# H204_R_Sensors.net
KiCad netlist of a schematic drawn in Altium Designer
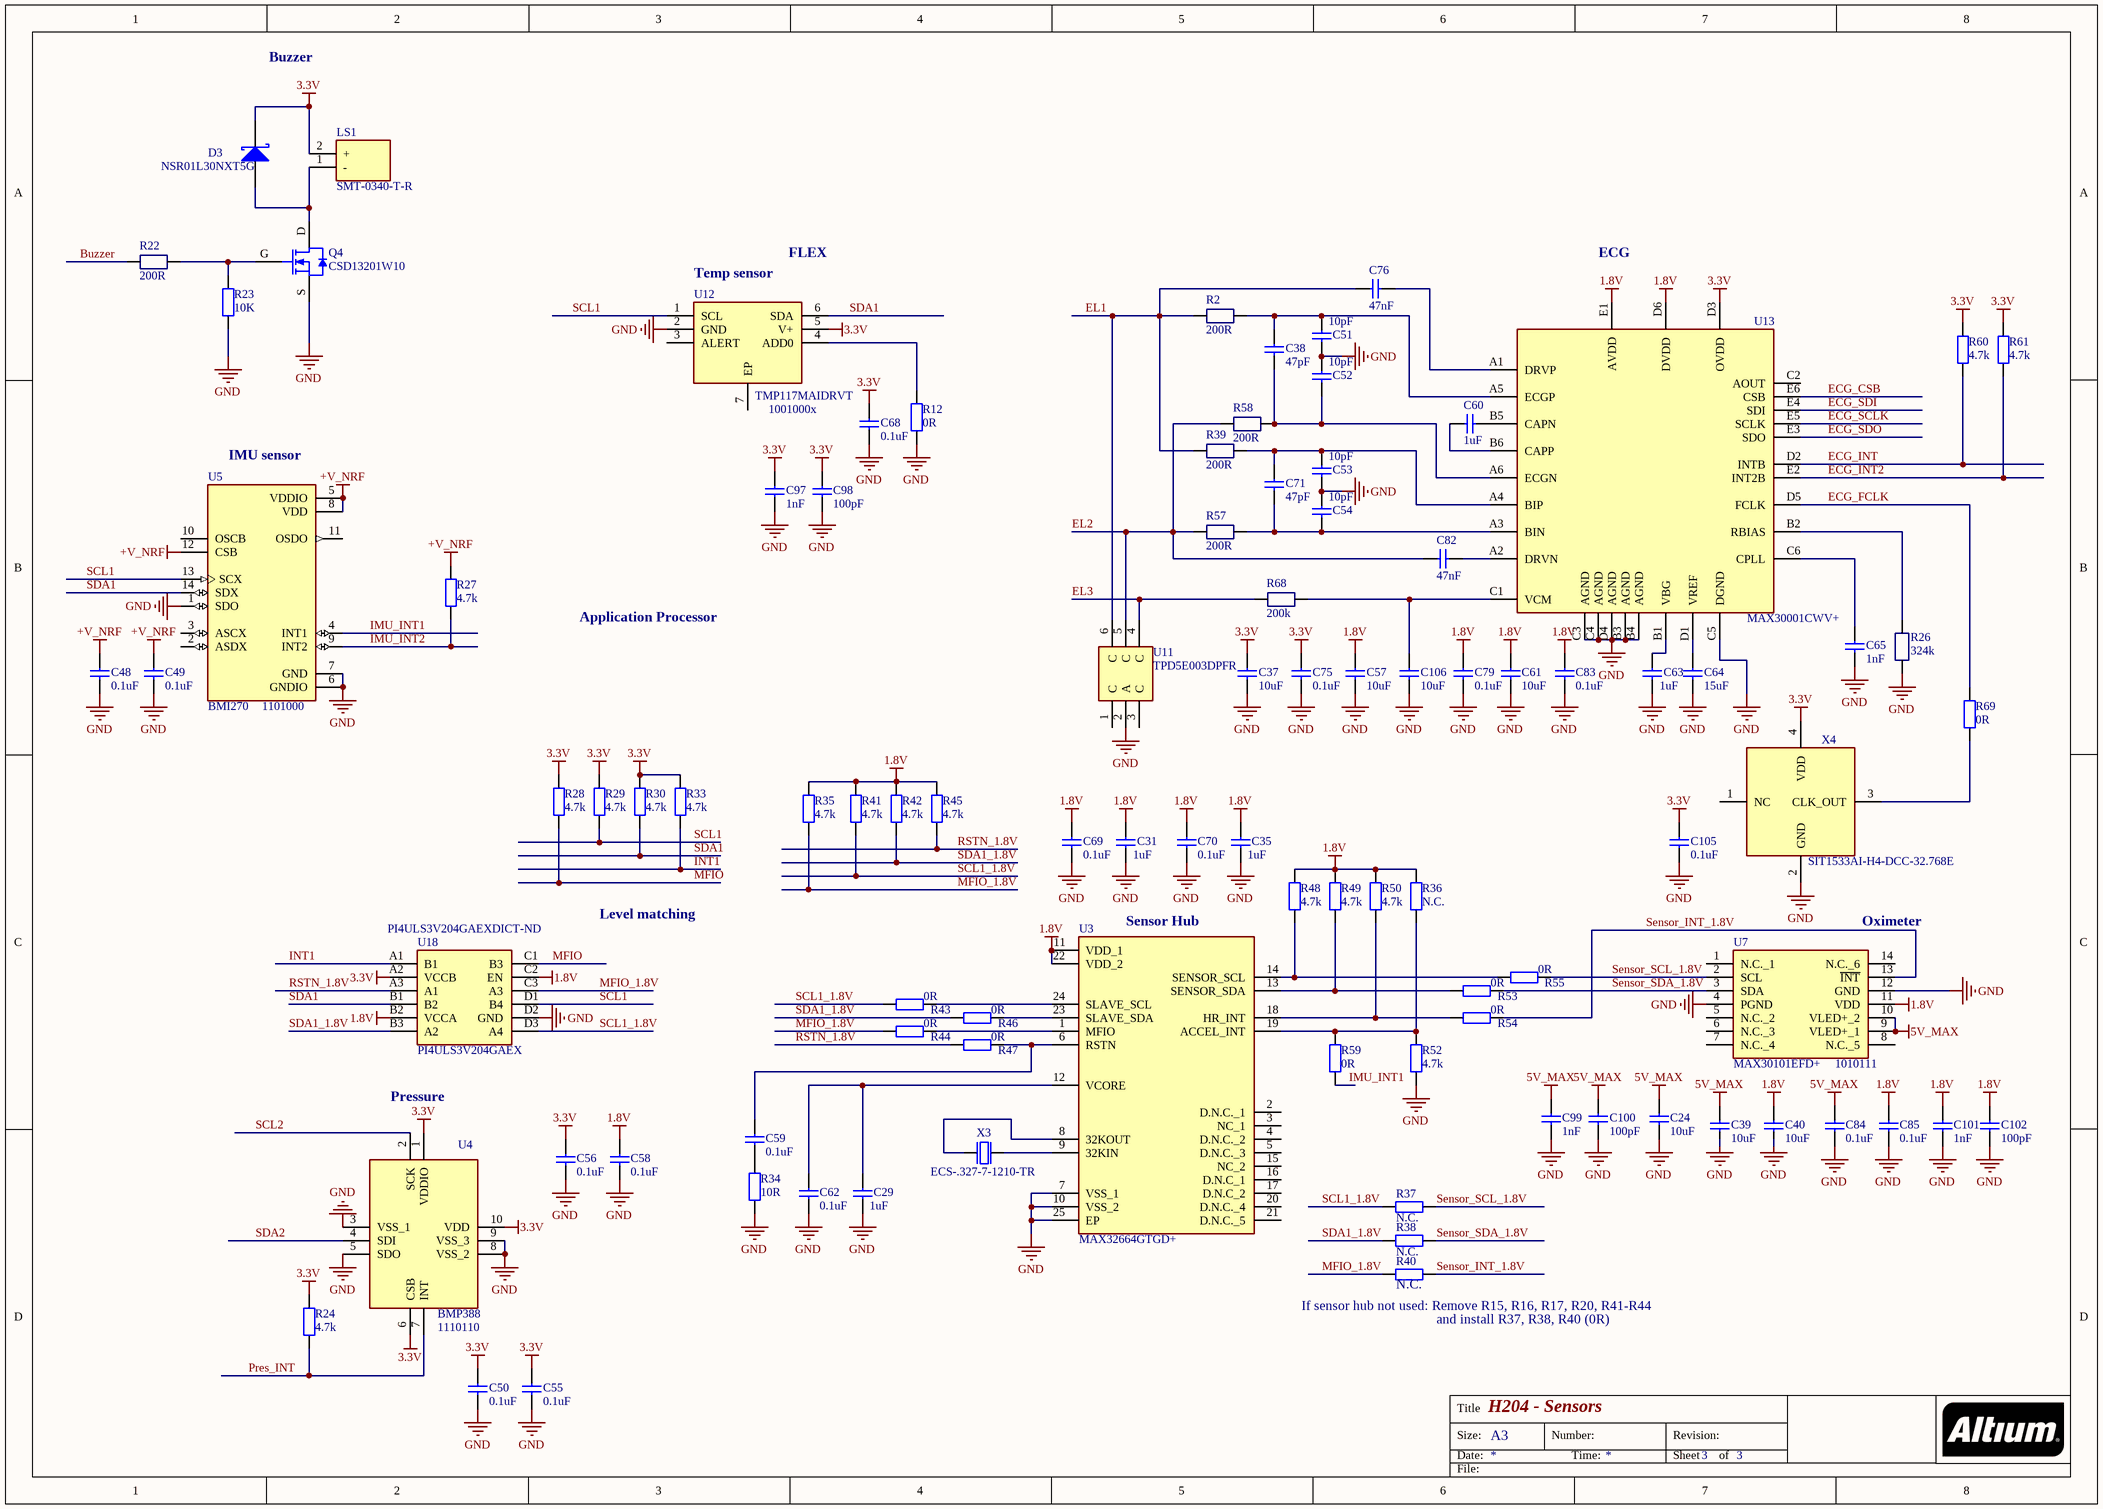
[diagram p0: H204_R_Sensors.SchDoc]

(export (version "E")
  (design (tool "Eeschema 10.0.6"))
  (components
    (comp (ref "C24")
      (value "10uF")
      (footprint "CAPC1005X55N")
      (description "CAP CER 10UF 10V X5R 0402")
      (fields
        (field (name "MANUFACTURER") "Samsung")
        (field (name "MANUFACTURER PART NUMBER") "CL05A106MP8NUB8")
      )
      (libsource (lib "Nordic Passive DB") (part "CAP"))
    )
    (comp (ref "C29")
      (value "1uF")
      (footprint "CAPC0603X33N")
      (description "CAP CER 1UF 6.3V X5R 0201")
      (fields
        (field (name "MANUFACTURER") "Samsung")
        (field (name "MANUFACTURER PART NUMBER") "CL03A105MQ3CSNC")
      )
      (libsource (lib "AltiumLib") (part "CAP"))
    )
    (comp (ref "C31")
      (value "1uF")
      (footprint "CAPC0603X33N")
      (description "CAP CER 1UF 6.3V X5R 0201")
      (fields
        (field (name "MANUFACTURER") "Samsung")
        (field (name "MANUFACTURER PART NUMBER") "CL03A105MQ3CSNC")
      )
      (libsource (lib "AltiumLib") (part "CAP"))
    )
    (comp (ref "C35")
      (value "1uF")
      (footprint "CAPC0603X33N")
      (description "CAP CER 1UF 6.3V X5R 0201")
      (fields
        (field (name "MANUFACTURER") "Samsung")
        (field (name "MANUFACTURER PART NUMBER") "CL03A105MQ3CSNC")
      )
      (libsource (lib "AltiumLib") (part "CAP"))
    )
    (comp (ref "C37")
      (value "10uF")
      (footprint "CAPC1005X55N")
      (description "CAP CER 10UF 10V X5R 0402")
      (fields
        (field (name "MANUFACTURER") "Samsung")
        (field (name "MANUFACTURER PART NUMBER") "CL05A106MP8NUB8")
      )
      (libsource (lib "Nordic Passive DB") (part "CAP"))
    )
    (comp (ref "C38")
      (value "47pF")
      (footprint "CAPC0603X33N")
      (description "Cap Ceramic Monolithic 47pF 50VDC 1% SMD Paper T/R")
      (fields
        (field (name "MANUFACTURER") "Murata")
        (field (name "MANUFACTURER PART NUMBER") "GRM0335C1H470FA01D")
      )
      (libsource (lib "Nordic Passive DB") (part "CAP"))
    )
    (comp (ref "C39")
      (value "10uF")
      (footprint "CAPC1005X55N")
      (description "CAP CER 10UF 10V X5R 0402")
      (fields
        (field (name "MANUFACTURER") "Samsung")
        (field (name "MANUFACTURER PART NUMBER") "CL05A106MP8NUB8")
      )
      (libsource (lib "Nordic Passive DB") (part "CAP"))
    )
    (comp (ref "C40")
      (value "10uF")
      (footprint "CAPC1005X55N")
      (description "CAP CER 10UF 10V X5R 0402")
      (fields
        (field (name "MANUFACTURER") "Samsung")
        (field (name "MANUFACTURER PART NUMBER") "CL05A106MP8NUB8")
      )
      (libsource (lib "Nordic Passive DB") (part "CAP"))
    )
    (comp (ref "C48")
      (value "0.1uF")
      (footprint "CAPC0603X33N")
      (description "CAP CER 0.1UF 16V X5R 0201")
      (fields
        (field (name "MANUFACTURER") "Samsung")
        (field (name "MANUFACTURER PART NUMBER") "CL03A104KO3NNNC")
      )
      (libsource (lib "AltiumLib") (part "CAP"))
    )
    (comp (ref "C49")
      (value "0.1uF")
      (footprint "CAPC0603X33N")
      (description "CAP CER 0.1UF 16V X5R 0201")
      (fields
        (field (name "MANUFACTURER") "Samsung")
        (field (name "MANUFACTURER PART NUMBER") "CL03A104KO3NNNC")
      )
      (libsource (lib "AltiumLib") (part "CAP"))
    )
    (comp (ref "C50")
      (value "0.1uF")
      (footprint "CAPC0603X33N")
      (description "CAP CER 0.1UF 16V X5R 0201")
      (fields
        (field (name "MANUFACTURER") "Samsung")
        (field (name "MANUFACTURER PART NUMBER") "CL03A104KO3NNNC")
      )
      (libsource (lib "AltiumLib") (part "CAP"))
    )
    (comp (ref "C51")
      (value "10pF")
      (footprint "CAPC0603X33N")
      (fields
        (field (name "MANUFACTURER") "Murata")
        (field (name "MANUFACTURER PART NUMBER") "GRM0335C1H100JA01D")
        (field (name "TOLERANCE") "5%")
      )
      (libsource (lib "Nordic Passive DB") (part "CAP"))
    )
    (comp (ref "C52")
      (value "10pF")
      (footprint "CAPC0603X33N")
      (fields
        (field (name "MANUFACTURER") "Murata")
        (field (name "MANUFACTURER PART NUMBER") "GRM0335C1H100JA01D")
        (field (name "TOLERANCE") "5%")
      )
      (libsource (lib "Nordic Passive DB") (part "CAP"))
    )
    (comp (ref "C53")
      (value "10pF")
      (footprint "CAPC0603X33N")
      (fields
        (field (name "MANUFACTURER") "Murata")
        (field (name "MANUFACTURER PART NUMBER") "GRM0335C1H100JA01D")
        (field (name "TOLERANCE") "5%")
      )
      (libsource (lib "Nordic Passive DB") (part "CAP"))
    )
    (comp (ref "C54")
      (value "10pF")
      (footprint "CAPC0603X33N")
      (fields
        (field (name "MANUFACTURER") "Murata")
        (field (name "MANUFACTURER PART NUMBER") "GRM0335C1H100JA01D")
        (field (name "TOLERANCE") "5%")
      )
      (libsource (lib "Nordic Passive DB") (part "CAP"))
    )
    (comp (ref "C55")
      (value "0.1uF")
      (footprint "CAPC0603X33N")
      (description "CAP CER 0.1UF 16V X5R 0201")
      (fields
        (field (name "MANUFACTURER") "Samsung")
        (field (name "MANUFACTURER PART NUMBER") "CL03A104KO3NNNC")
      )
      (libsource (lib "AltiumLib") (part "CAP"))
    )
    (comp (ref "C56")
      (value "0.1uF")
      (footprint "CAPC0603X33N")
      (description "CAP CER 0.1UF 16V X5R 0201")
      (fields
        (field (name "MANUFACTURER") "Samsung")
        (field (name "MANUFACTURER PART NUMBER") "CL03A104KO3NNNC")
      )
      (libsource (lib "AltiumLib") (part "CAP"))
    )
    (comp (ref "C57")
      (value "10uF")
      (footprint "CAPC1005X55N")
      (description "CAP CER 10UF 10V X5R 0402")
      (fields
        (field (name "MANUFACTURER") "Samsung")
        (field (name "MANUFACTURER PART NUMBER") "CL05A106MP8NUB8")
      )
      (libsource (lib "Nordic Passive DB") (part "CAP"))
    )
    (comp (ref "C58")
      (value "0.1uF")
      (footprint "CAPC0603X33N")
      (description "CAP CER 0.1UF 16V X5R 0201")
      (fields
        (field (name "MANUFACTURER") "Samsung")
        (field (name "MANUFACTURER PART NUMBER") "CL03A104KO3NNNC")
      )
      (libsource (lib "AltiumLib") (part "CAP"))
    )
    (comp (ref "C59")
      (value "0.1uF")
      (footprint "CAPC0603X33N")
      (description "CAP CER 0.1UF 16V X5R 0201")
      (fields
        (field (name "MANUFACTURER") "Samsung")
        (field (name "MANUFACTURER PART NUMBER") "CL03A104KO3NNNC")
      )
      (libsource (lib "AltiumLib") (part "CAP"))
    )
    (comp (ref "C60")
      (value "1uF")
      (footprint "CAPC0603X33N")
      (description "CAP CER 1UF 6.3V X5R 0201")
      (fields
        (field (name "MANUFACTURER") "Samsung")
        (field (name "MANUFACTURER PART NUMBER") "CL03A105MQ3CSNC")
      )
      (libsource (lib "AltiumLib") (part "CAP"))
    )
    (comp (ref "C61")
      (value "10uF")
      (footprint "CAPC1005X55N")
      (description "CAP CER 10UF 10V X5R 0402")
      (fields
        (field (name "MANUFACTURER") "Samsung")
        (field (name "MANUFACTURER PART NUMBER") "CL05A106MP8NUB8")
      )
      (libsource (lib "Nordic Passive DB") (part "CAP"))
    )
    (comp (ref "C62")
      (value "0.1uF")
      (footprint "CAPC0603X33N")
      (description "CAP CER 0.1UF 16V X5R 0201")
      (fields
        (field (name "MANUFACTURER") "Samsung")
        (field (name "MANUFACTURER PART NUMBER") "CL03A104KO3NNNC")
      )
      (libsource (lib "AltiumLib") (part "CAP"))
    )
    (comp (ref "C63")
      (value "1uF")
      (footprint "CAPC0603X33N")
      (description "CAP CER 1UF 6.3V X5R 0201")
      (fields
        (field (name "MANUFACTURER") "Samsung")
        (field (name "MANUFACTURER PART NUMBER") "CL03A105MQ3CSNC")
      )
      (libsource (lib "AltiumLib") (part "CAP"))
    )
    (comp (ref "C64")
      (value "15uF")
      (footprint "CAPC1005X55N")
      (description "Cap Ceramic Monolithic 15uF 6.3VDC 20% SMD Paper T/R")
      (fields
        (field (name "MANUFACTURER") "Murata")
        (field (name "MANUFACTURER PART NUMBER") "GRM155R60J156ME05D")
      )
      (libsource (lib "Nordic Passive DB") (part "CAP"))
    )
    (comp (ref "C65")
      (value "1nF")
      (footprint "CAPC0603X33N")
      (description "Cap Ceramic 0.001uF 25V X7R 10% SMD 0201 125C Paper T/R")
      (fields
        (field (name "MANUFACTURER") "Samsung")
        (field (name "MANUFACTURER PART NUMBER") "CL03B102KA3NNNC")
      )
      (libsource (lib "Nordic Passive DB") (part "CAP"))
    )
    (comp (ref "C68")
      (value "0.1uF")
      (footprint "CAPC0603X33N")
      (description "CAP CER 0.1UF 16V X5R 0201")
      (fields
        (field (name "MANUFACTURER") "Samsung")
        (field (name "MANUFACTURER PART NUMBER") "CL03A104KO3NNNC")
      )
      (libsource (lib "AltiumLib") (part "CAP"))
    )
    (comp (ref "C69")
      (value "0.1uF")
      (footprint "CAPC0603X33N")
      (description "CAP CER 0.1UF 16V X5R 0201")
      (fields
        (field (name "MANUFACTURER") "Samsung")
        (field (name "MANUFACTURER PART NUMBER") "CL03A104KO3NNNC")
      )
      (libsource (lib "AltiumLib") (part "CAP"))
    )
    (comp (ref "C70")
      (value "0.1uF")
      (footprint "CAPC0603X33N")
      (description "CAP CER 0.1UF 16V X5R 0201")
      (fields
        (field (name "MANUFACTURER") "Samsung")
        (field (name "MANUFACTURER PART NUMBER") "CL03A104KO3NNNC")
      )
      (libsource (lib "AltiumLib") (part "CAP"))
    )
    (comp (ref "C71")
      (value "47pF")
      (footprint "CAPC0603X33N")
      (description "Cap Ceramic Monolithic 47pF 50VDC 1% SMD Paper T/R")
      (fields
        (field (name "MANUFACTURER") "Murata")
        (field (name "MANUFACTURER PART NUMBER") "GRM0335C1H470FA01D")
      )
      (libsource (lib "Nordic Passive DB") (part "CAP"))
    )
    (comp (ref "C75")
      (value "0.1uF")
      (footprint "CAPC0603X33N")
      (description "CAP CER 0.1UF 16V X5R 0201")
      (fields
        (field (name "MANUFACTURER") "Samsung")
        (field (name "MANUFACTURER PART NUMBER") "CL03A104KO3NNNC")
      )
      (libsource (lib "AltiumLib") (part "CAP"))
    )
    (comp (ref "C76")
      (value "47nF")
      (footprint "CAPC0603X33N")
      (description "CAP CER 0.047UF 25V X5R 0201")
      (fields
        (field (name "MANUFACTURER") "TDK")
        (field (name "MANUFACTURER PART NUMBER") "C0603X5R1E473K030BB")
      )
      (libsource (lib "Nordic Passive DB") (part "CAP"))
    )
    (comp (ref "C79")
      (value "0.1uF")
      (footprint "CAPC0603X33N")
      (description "CAP CER 0.1UF 16V X5R 0201")
      (fields
        (field (name "MANUFACTURER") "Samsung")
        (field (name "MANUFACTURER PART NUMBER") "CL03A104KO3NNNC")
      )
      (libsource (lib "AltiumLib") (part "CAP"))
    )
    (comp (ref "C82")
      (value "47nF")
      (footprint "CAPC0603X33N")
      (description "CAP CER 0.047UF 25V X5R 0201")
      (fields
        (field (name "MANUFACTURER") "TDK")
        (field (name "MANUFACTURER PART NUMBER") "C0603X5R1E473K030BB")
      )
      (libsource (lib "Nordic Passive DB") (part "CAP"))
    )
    (comp (ref "C83")
      (value "0.1uF")
      (footprint "CAPC0603X33N")
      (description "CAP CER 0.1UF 16V X5R 0201")
      (fields
        (field (name "MANUFACTURER") "Samsung")
        (field (name "MANUFACTURER PART NUMBER") "CL03A104KO3NNNC")
      )
      (libsource (lib "AltiumLib") (part "CAP"))
    )
    (comp (ref "C84")
      (value "0.1uF")
      (footprint "CAPC0603X33N")
      (description "CAP CER 0.1UF 16V X5R 0201")
      (fields
        (field (name "MANUFACTURER") "Samsung")
        (field (name "MANUFACTURER PART NUMBER") "CL03A104KO3NNNC")
      )
      (libsource (lib "AltiumLib") (part "CAP"))
    )
    (comp (ref "C85")
      (value "0.1uF")
      (footprint "CAPC0603X33N")
      (description "CAP CER 0.1UF 16V X5R 0201")
      (fields
        (field (name "MANUFACTURER") "Samsung")
        (field (name "MANUFACTURER PART NUMBER") "CL03A104KO3NNNC")
      )
      (libsource (lib "AltiumLib") (part "CAP"))
    )
    (comp (ref "C97")
      (value "1nF")
      (footprint "CAPC0603X33N")
      (description "Cap Ceramic 0.001uF 25V X7R 10% SMD 0201 125C Paper T/R")
      (fields
        (field (name "MANUFACTURER") "Samsung")
        (field (name "MANUFACTURER PART NUMBER") "CL03B102KA3NNNC")
      )
      (libsource (lib "Nordic Passive DB") (part "CAP"))
    )
    (comp (ref "C98")
      (value "100pF")
      (footprint "CAPC0603X33N")
      (description "CAP CER 100PF 50V C0G 0201")
      (fields
        (field (name "MANUFACTURER") "TDK")
        (field (name "MANUFACTURER PART NUMBER") "C0603C0G1H101J030BA")
      )
      (libsource (lib "Nordic Passive DB") (part "CAP"))
    )
    (comp (ref "C99")
      (value "1nF")
      (footprint "CAPC0603X33N")
      (description "Cap Ceramic 0.001uF 25V X7R 10% SMD 0201 125C Paper T/R")
      (fields
        (field (name "MANUFACTURER") "Samsung")
        (field (name "MANUFACTURER PART NUMBER") "CL03B102KA3NNNC")
      )
      (libsource (lib "Nordic Passive DB") (part "CAP"))
    )
    (comp (ref "C100")
      (value "100pF")
      (footprint "CAPC0603X33N")
      (description "CAP CER 100PF 50V C0G 0201")
      (fields
        (field (name "MANUFACTURER") "TDK")
        (field (name "MANUFACTURER PART NUMBER") "C0603C0G1H101J030BA")
      )
      (libsource (lib "Nordic Passive DB") (part "CAP"))
    )
    (comp (ref "C101")
      (value "1nF")
      (footprint "CAPC0603X33N")
      (description "Cap Ceramic 0.001uF 25V X7R 10% SMD 0201 125C Paper T/R")
      (fields
        (field (name "MANUFACTURER") "Samsung")
        (field (name "MANUFACTURER PART NUMBER") "CL03B102KA3NNNC")
      )
      (libsource (lib "Nordic Passive DB") (part "CAP"))
    )
    (comp (ref "C102")
      (value "100pF")
      (footprint "CAPC0603X33N")
      (description "CAP CER 100PF 50V C0G 0201")
      (fields
        (field (name "MANUFACTURER") "TDK")
        (field (name "MANUFACTURER PART NUMBER") "C0603C0G1H101J030BA")
      )
      (libsource (lib "Nordic Passive DB") (part "CAP"))
    )
    (comp (ref "C105")
      (value "0.1uF")
      (footprint "CAPC0603X33N")
      (description "CAP CER 0.1UF 16V X5R 0201")
      (fields
        (field (name "MANUFACTURER") "Samsung")
        (field (name "MANUFACTURER PART NUMBER") "CL03A104KO3NNNC")
      )
      (libsource (lib "AltiumLib") (part "CAP"))
    )
    (comp (ref "C106")
      (value "10uF")
      (footprint "CAPC1005X55N")
      (description "CAP CER 10UF 10V X5R 0402")
      (fields
        (field (name "MANUFACTURER") "Samsung")
        (field (name "MANUFACTURER PART NUMBER") "CL05A106MP8NUB8")
      )
      (libsource (lib "Nordic Passive DB") (part "CAP"))
    )
    (comp (ref "D3")
      (value "NSR01L30NXT5G")
      (footprint "NSR01L30NXT5G")
      (fields (field (name "MANUFACTURER") "ON Semiconductor"))
      (libsource (lib "Diodes - Bridge Rectifiers") (part "Schottky"))
    )
    (comp (ref "LS1")
      (value "SMT-0340-T-R")
      (footprint "SMT0340TR")
      (description "Loudspeaker or Buzzer")
      (fields
        (field (name "MANUFACTURER") "PUI Audio")
        (field (name "MOUSER PART NUMBER") "665-SMT-0340-T-R")
      )
      (libsource (lib "*") (part "SMT-0340-T-R"))
    )
    (comp (ref "Q4")
      (value "CSD13201W10")
      (footprint "CSD13201W10")
      (description "12V, N ch NexFET MOSFET™, single WLP 1.0x1.0, 34mOhm 4-DSBGA -55 to 150")
      (fields (field (name "MANUFACTURER") "Texas Instruments"))
      (libsource (lib "Transistors") (part "Transistor N-channel"))
    )
    (comp (ref "R2")
      (value "200R")
      (footprint "RESC0603X26N")
      (description "RES SMD 200 OHM 1% 1/20W 0201")
      (fields
        (field (name "MANUFACTURER") "Yageo")
        (field (name "MANUFACTURER PART NUMBER") "RC0201FR-07200RL")
      )
      (libsource (lib "Passive components") (part "Resistor"))
    )
    (comp (ref "R12")
      (value "0R")
      (footprint "RESC0603X26N")
      (description "Fixed Resistor, Metal Glaze/thick Film, 0.05W, 0ohm, Surface Mount, 0201")
      (fields
        (field (name "MANUFACTURER") "Yageo")
        (field (name "MANUFACTURER PART NUMBER") "AF0201JR-070RL")
      )
      (libsource (lib "") (part "Res2_2"))
    )
    (comp (ref "R22")
      (value "200R")
      (footprint "RESC0603X26N")
      (description "RES SMD 200 OHM 1% 1/20W 0201")
      (fields
        (field (name "MANUFACTURER") "Yageo")
        (field (name "MANUFACTURER PART NUMBER") "RC0201FR-07200RL")
      )
      (libsource (lib "Passive components") (part "Resistor"))
    )
    (comp (ref "R23")
      (value "10K")
      (footprint "RESC0603X26N")
      (description "GENERAL 0201 11% REEL (7INCH)")
      (fields
        (field (name "MANUFACTURER") "Yageo")
        (field (name "MANUFACTURER PART NUMBER") "RC0201FR-0710KL")
      )
      (libsource (lib "") (part "Res2_3"))
    )
    (comp (ref "R24")
      (value "4.7k")
      (footprint "RESC0603X26N")
      (description "GENERAL 0201 11% REEL (7INCH)")
      (fields
        (field (name "MANUFACTURER") "Yageo")
        (field (name "MANUFACTURER PART NUMBER") "RC0201FR-074K7L")
      )
      (libsource (lib "Miscellaneous Devices") (part "Res2"))
    )
    (comp (ref "R26")
      (value "324k")
      (footprint "RESC0603X26N")
      (description "Res Thick Film 0201 324K Ohm 1% 1/20W ±200ppm/°C Molded SMD Paper T/R")
      (fields
        (field (name "MANUFACTURER") "Yageo")
        (field (name "MANUFACTURER PART NUMBER") "RC0201FR-07324KL")
      )
      (libsource (lib "Passive components") (part "Resistor"))
    )
    (comp (ref "R27")
      (value "4.7k")
      (footprint "RESC0603X26N")
      (description "GENERAL 0201 11% REEL (7INCH)")
      (fields
        (field (name "MANUFACTURER") "Yageo")
        (field (name "MANUFACTURER PART NUMBER") "RC0201FR-074K7L")
      )
      (libsource (lib "Miscellaneous Devices") (part "Res2"))
    )
    (comp (ref "R28")
      (value "4.7k")
      (footprint "RESC0603X26N")
      (description "GENERAL 0201 11% REEL (7INCH)")
      (fields
        (field (name "MANUFACTURER") "Yageo")
        (field (name "MANUFACTURER PART NUMBER") "RC0201FR-074K7L")
      )
      (libsource (lib "Miscellaneous Devices") (part "Res2"))
    )
    (comp (ref "R29")
      (value "4.7k")
      (footprint "RESC0603X26N")
      (description "GENERAL 0201 11% REEL (7INCH)")
      (fields
        (field (name "MANUFACTURER") "Yageo")
        (field (name "MANUFACTURER PART NUMBER") "RC0201FR-074K7L")
      )
      (libsource (lib "Miscellaneous Devices") (part "Res2"))
    )
    (comp (ref "R30")
      (value "4.7k")
      (footprint "RESC0603X26N")
      (description "GENERAL 0201 11% REEL (7INCH)")
      (fields
        (field (name "MANUFACTURER") "Yageo")
        (field (name "MANUFACTURER PART NUMBER") "RC0201FR-074K7L")
      )
      (libsource (lib "Miscellaneous Devices") (part "Res2"))
    )
    (comp (ref "R33")
      (value "4.7k")
      (footprint "RESC0603X26N")
      (description "GENERAL 0201 11% REEL (7INCH)")
      (fields
        (field (name "MANUFACTURER") "Yageo")
        (field (name "MANUFACTURER PART NUMBER") "RC0201FR-074K7L")
      )
      (libsource (lib "Miscellaneous Devices") (part "Res2"))
    )
    (comp (ref "R34")
      (value "10R")
      (footprint "RESC0603X26N")
      (description "RES SMD 10 OHM 1% 1/20W 0201")
      (fields
        (field (name "MANUFACTURER") "Yageo")
        (field (name "MANUFACTURER PART NUMBER") "RC0201FR-0710RL")
      )
      (libsource (lib "") (part "Res2_3"))
    )
    (comp (ref "R35")
      (value "4.7k")
      (footprint "RESC0603X26N")
      (description "GENERAL 0201 11% REEL (7INCH)")
      (fields
        (field (name "MANUFACTURER") "Yageo")
        (field (name "MANUFACTURER PART NUMBER") "RC0201FR-074K7L")
      )
      (libsource (lib "Miscellaneous Devices") (part "Res2"))
    )
    (comp (ref "R36")
      (value "N.C.")
      (footprint "RESC0603X26N")
      (description "Resistor")
      (libsource (lib "") (part "Res2_3"))
    )
    (comp (ref "R37")
      (value "N.C.")
      (footprint "RESC0603X26N")
      (description "Resistor")
      (libsource (lib "Miscellaneous Devices") (part "Res2"))
    )
    (comp (ref "R38")
      (value "N.C.")
      (footprint "RESC0603X26N")
      (description "Resistor")
      (libsource (lib "Miscellaneous Devices") (part "Res2"))
    )
    (comp (ref "R39")
      (value "200R")
      (footprint "RESC0603X26N")
      (description "RES SMD 200 OHM 1% 1/20W 0201")
      (fields
        (field (name "MANUFACTURER") "Yageo")
        (field (name "MANUFACTURER PART NUMBER") "RC0201FR-07200RL")
      )
      (libsource (lib "Passive components") (part "Resistor"))
    )
    (comp (ref "R40")
      (value "N.C.")
      (footprint "RESC0603X26N")
      (description "Resistor")
      (libsource (lib "Miscellaneous Devices") (part "Res2"))
    )
    (comp (ref "R41")
      (value "4.7k")
      (footprint "RESC0603X26N")
      (description "GENERAL 0201 11% REEL (7INCH)")
      (fields
        (field (name "MANUFACTURER") "Yageo")
        (field (name "MANUFACTURER PART NUMBER") "RC0201FR-074K7L")
      )
      (libsource (lib "Miscellaneous Devices") (part "Res2"))
    )
    (comp (ref "R42")
      (value "4.7k")
      (footprint "RESC0603X26N")
      (description "GENERAL 0201 11% REEL (7INCH)")
      (fields
        (field (name "MANUFACTURER") "Yageo")
        (field (name "MANUFACTURER PART NUMBER") "RC0201FR-074K7L")
      )
      (libsource (lib "Miscellaneous Devices") (part "Res2"))
    )
    (comp (ref "R43")
      (value "0R")
      (footprint "RESC0603X26N")
      (description "Fixed Resistor, Metal Glaze/thick Film, 0.05W, 0ohm, Surface Mount, 0201")
      (fields
        (field (name "MANUFACTURER") "Yageo")
        (field (name "MANUFACTURER PART NUMBER") "AF0201JR-070RL")
      )
      (libsource (lib "") (part "Res2_1"))
    )
    (comp (ref "R44")
      (value "0R")
      (footprint "RESC0603X26N")
      (description "Fixed Resistor, Metal Glaze/thick Film, 0.05W, 0ohm, Surface Mount, 0201")
      (fields
        (field (name "MANUFACTURER") "Yageo")
        (field (name "MANUFACTURER PART NUMBER") "AF0201JR-070RL")
      )
      (libsource (lib "") (part "Res2_1"))
    )
    (comp (ref "R45")
      (value "4.7k")
      (footprint "RESC0603X26N")
      (description "GENERAL 0201 11% REEL (7INCH)")
      (fields
        (field (name "MANUFACTURER") "Yageo")
        (field (name "MANUFACTURER PART NUMBER") "RC0201FR-074K7L")
      )
      (libsource (lib "Miscellaneous Devices") (part "Res2"))
    )
    (comp (ref "R46")
      (value "0R")
      (footprint "RESC0603X26N")
      (description "Fixed Resistor, Metal Glaze/thick Film, 0.05W, 0ohm, Surface Mount, 0201")
      (fields
        (field (name "MANUFACTURER") "Yageo")
        (field (name "MANUFACTURER PART NUMBER") "AF0201JR-070RL")
      )
      (libsource (lib "") (part "Res2_1"))
    )
    (comp (ref "R47")
      (value "0R")
      (footprint "RESC0603X26N")
      (description "Fixed Resistor, Metal Glaze/thick Film, 0.05W, 0ohm, Surface Mount, 0201")
      (fields
        (field (name "MANUFACTURER") "Yageo")
        (field (name "MANUFACTURER PART NUMBER") "AF0201JR-070RL")
      )
      (libsource (lib "") (part "Res2_1"))
    )
    (comp (ref "R48")
      (value "4.7k")
      (footprint "RESC0603X26N")
      (description "GENERAL 0201 11% REEL (7INCH)")
      (fields
        (field (name "MANUFACTURER") "Yageo")
        (field (name "MANUFACTURER PART NUMBER") "RC0201FR-074K7L")
      )
      (libsource (lib "Miscellaneous Devices") (part "Res2"))
    )
    (comp (ref "R49")
      (value "4.7k")
      (footprint "RESC0603X26N")
      (description "GENERAL 0201 11% REEL (7INCH)")
      (fields
        (field (name "MANUFACTURER") "Yageo")
        (field (name "MANUFACTURER PART NUMBER") "RC0201FR-074K7L")
      )
      (libsource (lib "Miscellaneous Devices") (part "Res2"))
    )
    (comp (ref "R50")
      (value "4.7k")
      (footprint "RESC0603X26N")
      (description "GENERAL 0201 11% REEL (7INCH)")
      (fields
        (field (name "MANUFACTURER") "Yageo")
        (field (name "MANUFACTURER PART NUMBER") "RC0201FR-074K7L")
      )
      (libsource (lib "Miscellaneous Devices") (part "Res2"))
    )
    (comp (ref "R52")
      (value "4.7k")
      (footprint "RESC0603X26N")
      (description "GENERAL 0201 11% REEL (7INCH)")
      (fields
        (field (name "MANUFACTURER") "Yageo")
        (field (name "MANUFACTURER PART NUMBER") "RC0201FR-074K7L")
      )
      (libsource (lib "Miscellaneous Devices") (part "Res2"))
    )
    (comp (ref "R53")
      (value "0R")
      (footprint "RESC0603X26N")
      (description "Fixed Resistor, Metal Glaze/thick Film, 0.05W, 0ohm, Surface Mount, 0201")
      (fields
        (field (name "MANUFACTURER") "Yageo")
        (field (name "MANUFACTURER PART NUMBER") "AF0201JR-070RL")
      )
      (libsource (lib "") (part "Res2_1"))
    )
    (comp (ref "R54")
      (value "0R")
      (footprint "RESC0603X26N")
      (description "Fixed Resistor, Metal Glaze/thick Film, 0.05W, 0ohm, Surface Mount, 0201")
      (fields
        (field (name "MANUFACTURER") "Yageo")
        (field (name "MANUFACTURER PART NUMBER") "AF0201JR-070RL")
      )
      (libsource (lib "") (part "Res2_1"))
    )
    (comp (ref "R55")
      (value "0R")
      (footprint "RESC0603X26N")
      (description "Fixed Resistor, Metal Glaze/thick Film, 0.05W, 0ohm, Surface Mount, 0201")
      (fields
        (field (name "MANUFACTURER") "Yageo")
        (field (name "MANUFACTURER PART NUMBER") "AF0201JR-070RL")
      )
      (libsource (lib "") (part "Res2_1"))
    )
    (comp (ref "R57")
      (value "200R")
      (footprint "RESC0603X26N")
      (description "RES SMD 200 OHM 1% 1/20W 0201")
      (fields
        (field (name "MANUFACTURER") "Yageo")
        (field (name "MANUFACTURER PART NUMBER") "RC0201FR-07200RL")
      )
      (libsource (lib "Passive components") (part "Resistor"))
    )
    (comp (ref "R58")
      (value "200R")
      (footprint "RESC0603X26N")
      (description "RES SMD 200 OHM 1% 1/20W 0201")
      (fields
        (field (name "MANUFACTURER") "Yageo")
        (field (name "MANUFACTURER PART NUMBER") "RC0201FR-07200RL")
      )
      (libsource (lib "Passive components") (part "Resistor"))
    )
    (comp (ref "R59")
      (value "0R")
      (footprint "RESC0603X26N")
      (description "Fixed Resistor, Metal Glaze/thick Film, 0.05W, 0ohm, Surface Mount, 0201")
      (fields
        (field (name "MANUFACTURER") "Yageo")
        (field (name "MANUFACTURER PART NUMBER") "AF0201JR-070RL")
      )
      (libsource (lib "Miscellaneous Devices") (part "Res2"))
    )
    (comp (ref "R60")
      (value "4.7k")
      (footprint "RESC0603X26N")
      (description "GENERAL 0201 11% REEL (7INCH)")
      (fields
        (field (name "MANUFACTURER") "Yageo")
        (field (name "MANUFACTURER PART NUMBER") "RC0201FR-074K7L")
      )
      (libsource (lib "Miscellaneous Devices") (part "Res2"))
    )
    (comp (ref "R61")
      (value "4.7k")
      (footprint "RESC0603X26N")
      (description "GENERAL 0201 11% REEL (7INCH)")
      (fields
        (field (name "MANUFACTURER") "Yageo")
        (field (name "MANUFACTURER PART NUMBER") "RC0201FR-074K7L")
      )
      (libsource (lib "Miscellaneous Devices") (part "Res2"))
    )
    (comp (ref "R68")
      (value "200k")
      (footprint "RESC0603X26N")
      (description "Thick Film Resistors - SMD 200K OHM 1%")
      (fields
        (field (name "MANUFACTURER") "Yageo")
        (field (name "MANUFACTURER PART NUMBER") "RC0201FR-07200KL")
      )
      (libsource (lib "Passive components") (part "Resistor"))
    )
    (comp (ref "R69")
      (value "0R")
      (footprint "RESC0603X26N")
      (description "Fixed Resistor, Metal Glaze/thick Film, 0.05W, 0ohm, Surface Mount, 0201")
      (fields
        (field (name "MANUFACTURER") "Yageo")
        (field (name "MANUFACTURER PART NUMBER") "AF0201JR-070RL")
      )
      (libsource (lib "") (part "Res2_2"))
    )
    (comp (ref "U3")
      (value "MAX32664GTGD+")
      (footprint "SamacSys:MAX32664GTGD")
      (description "Integrated Circuit")
      (fields (field (name "MANUFACTURER") "Maxim"))
      (libsource (lib "SamacSys") (part "MAX32664GTGD+"))
    )
    (comp (ref "U4")
      (value "BMP388")
      (footprint "SamacSys:BMP388")
      (description "Pressure Sensor 30kPa to 125kPa Absolute 10-Pin LGA")
      (fields (field (name "MANUFACTURER") "Bosch Sensortec") (field (name "TOLERANCE") "20%"))
      (libsource (lib "*") (part "BMP388"))
    )
    (comp (ref "U5")
      (value "BMI270")
      (footprint "XDCR_BMI270")
      (description "BMI270 Series 3.6 V 685 µA Smart Ultra-low Power Inertial Measurement Unit")
      (fields (field (name "MANUFACTURER") "Bosch Sensortec"))
      (libsource (lib "SnapEDAsch") (part "BMI270"))
    )
    (comp (ref "U7")
      (value "MAX30101EFD+")
      (footprint "SamacSys:14-LEAD-OESIP")
      (description "Analog Circuit, 1 Func")
      (fields (field (name "MANUFACTURER") "Maxim"))
      (libsource (lib "*") (part "MAX30101EFD+"))
    )
    (comp (ref "U11")
      (value "TPD5E003DPFR")
      (footprint "SON35P100X100X40-6N")
      (description "ESD Suppressors Five CH Space Saving ESD Protect Device")
      (fields (field (name "MANUFACTURER") "Texas Instruments"))
      (libsource (lib "*") (part "SP0505BAJTG"))
    )
    (comp (ref "U12")
      (value "TMP117MAIDRVT")
      (footprint "SamacSys:SON65P200X200X80-7N")
      (description "±0.1°C accurate digital temperature sensor with integrated NV memory 6-WSON 0 to 85")
      (fields (field (name "MANUFACTURER") "Texas Instruments"))
      (libsource (lib "*") (part "TMP117MAIDRVT"))
    )
    (comp (ref "U13")
      (value "MAX30001CWV+")
      (footprint "SamacSys:BGA30C50P6X5_293X274X69")
      (description "Biopotential/bioz Afe, WLP-30")
      (fields (field (name "MOUSER PART NUMBER") "700-MAX30001CWV+") (field (name "MANUFACTURER") "Maxim"))
      (libsource (lib "SamacSys") (part "MAX30001CWV+"))
    )
    (comp (ref "U18")
      (value "PI4ULS3V204GAEX")
      (footprint "BGA12C50P3X4_137X187X62")
      (description "UNIVERSAL BI-DIRECTIONALEVEL")
      (fields
        (field (name "MOUSER PART NUMBER") "729-PI4ULS3V204GAEX")
        (field (name "SUPPLIER PART NUMBER 1") "PI4ULS3V204GAEXDICT-ND")
        (field (name "MANUFACTURER") "Diodes")
      )
      (libsource (lib "*") (part "PI4ULS3V204GAEX"))
    )
    (comp (ref "X3")
      (value "ECS-.327-7-1210-TR")
      (footprint "XTAL_ECS-.327-7-1210-TR")
      (description "Crystal 32.7680Khz 6Pf Smd / Tape & Reel (Tr) Rohs Compliant: Yes")
      (fields (field (name "MANUFACTURER") "ECS International"))
      (libsource (lib "Nordic Discrete DB") (part "XTAL_4-pin_grounded"))
    )
    (comp (ref "X4")
      (value "SIT1533AI-H4-DCC-32.768E")
      (footprint "SamacSys:SIT1533AIH4DCC32768E")
      (description "Oscillator MEMS 0.032768MHz ±100ppm (Stability) LVCMOS 52% 1.8V/2.5V/3.3V 4-Pin SMD T/R")
      (fields
        (field (name "MOUSER PART NUMBER") "788-1533AIH4DCC32.76")
        (field (name "MANUFACTURER") "SiTime")
      )
      (libsource (lib "*") (part "SIT1533AI-H4-DCC-32.768E"))
    )
  )
  (nets
    (net (code "1") (name "+V_NRF") (class "Default")
      (node (ref "C48") (pin "1") (pinfunction "1_1") (pintype "passive"))
      (node (ref "C49") (pin "1") (pinfunction "1_1") (pintype "passive"))
      (node (ref "R27") (pin "1") (pinfunction "1_1") (pintype "passive"))
      (node (ref "U5") (pin "12") (pinfunction "CSB_12") (pintype "passive"))
      (node (ref "U5") (pin "5") (pinfunction "VDDIO_5") (pintype "power_in"))
      (node (ref "U5") (pin "8") (pinfunction "VDD_8") (pintype "power_in"))
    )
    (net (code "2") (name "/Buzzer") (class "Default")
      (node (ref "R22") (pin "1") (pinfunction "1_1") (pintype "passive"))
    )
    (net (code "3") (name "/ECG_CSB") (class "Default")
      (node (ref "U13") (pin "E6") (pinfunction "CSB_E6") (pintype "passive"))
    )
    (net (code "4") (name "/ECG_FCLK") (class "Default")
      (node (ref "R69") (pin "2") (pinfunction "2_2") (pintype "passive"))
      (node (ref "U13") (pin "D5") (pinfunction "FCLK_D5") (pintype "passive"))
    )
    (net (code "5") (name "/ECG_INT") (class "Default")
      (node (ref "R60") (pin "2") (pinfunction "2_2") (pintype "passive"))
      (node (ref "U13") (pin "D2") (pinfunction "INTB_D2") (pintype "passive"))
    )
    (net (code "6") (name "/ECG_INT2") (class "Default")
      (node (ref "R61") (pin "2") (pinfunction "2_2") (pintype "passive"))
      (node (ref "U13") (pin "E2") (pinfunction "INT2B_E2") (pintype "passive"))
    )
    (net (code "7") (name "/ECG_SCLK") (class "Default")
      (node (ref "U13") (pin "E5") (pinfunction "SCLK_E5") (pintype "passive"))
    )
    (net (code "8") (name "/ECG_SDI") (class "Default")
      (node (ref "U13") (pin "E4") (pinfunction "SDI_E4") (pintype "passive"))
    )
    (net (code "9") (name "/ECG_SDO") (class "Default")
      (node (ref "U13") (pin "E3") (pinfunction "SDO_E3") (pintype "passive"))
    )
    (net (code "10") (name "/EL1") (class "Default")
      (node (ref "C76") (pin "2") (pinfunction "2_2") (pintype "passive"))
      (node (ref "R2") (pin "1") (pinfunction "1_1") (pintype "passive"))
      (node (ref "R39") (pin "1") (pinfunction "1_1") (pintype "passive"))
      (node (ref "U11") (pin "6") (pinfunction "C_6") (pintype "passive"))
    )
    (net (code "11") (name "/EL2") (class "Default")
      (node (ref "C82") (pin "2") (pinfunction "2_2") (pintype "passive"))
      (node (ref "R57") (pin "1") (pinfunction "1_1") (pintype "passive"))
      (node (ref "R58") (pin "1") (pinfunction "1_1") (pintype "passive"))
      (node (ref "U11") (pin "5") (pinfunction "C_5") (pintype "passive"))
    )
    (net (code "12") (name "/EL3") (class "Default")
      (node (ref "R68") (pin "2") (pinfunction "2_2") (pintype "passive"))
      (node (ref "U11") (pin "4") (pinfunction "C_4") (pintype "passive"))
    )
    (net (code "13") (name "/IMU_INT1") (class "Default")
      (node (ref "R59") (pin "2") (pinfunction "2_2") (pintype "passive"))
      (node (ref "U5") (pin "4") (pinfunction "INT1_4") (pintype "bidirectional"))
    )
    (net (code "14") (name "/IMU_INT2") (class "Default")
      (node (ref "R27") (pin "2") (pinfunction "2_2") (pintype "passive"))
      (node (ref "U5") (pin "9") (pinfunction "INT2_9") (pintype "bidirectional"))
    )
    (net (code "15") (name "/INT1") (class "Default")
      (node (ref "R33") (pin "2") (pinfunction "2_2") (pintype "passive"))
      (node (ref "U18") (pin "A1") (pinfunction "B1_A1") (pintype "passive"))
    )
    (net (code "16") (name "/MFIO") (class "Default")
      (node (ref "R28") (pin "2") (pinfunction "2_2") (pintype "passive"))
      (node (ref "U18") (pin "C1") (pinfunction "B3_C1") (pintype "passive"))
    )
    (net (code "17") (name "/MFIO_1.8V") (class "Default")
      (node (ref "R35") (pin "2") (pinfunction "2_2") (pintype "passive"))
      (node (ref "R40") (pin "2") (pinfunction "2_2") (pintype "passive"))
      (node (ref "R44") (pin "1") (pinfunction "1_1") (pintype "passive"))
      (node (ref "U18") (pin "C3") (pinfunction "A3_C3") (pintype "passive"))
    )
    (net (code "18") (name "/Pres_INT") (class "Default")
      (node (ref "R24") (pin "2") (pinfunction "2_2") (pintype "passive"))
      (node (ref "U4") (pin "7") (pinfunction "INT_7") (pintype "passive"))
    )
    (net (code "19") (name "/RSTN_1.8V") (class "Default")
      (node (ref "R45") (pin "2") (pinfunction "2_2") (pintype "passive"))
      (node (ref "R47") (pin "1") (pinfunction "1_1") (pintype "passive"))
      (node (ref "U18") (pin "A3") (pinfunction "A1_A3") (pintype "passive"))
    )
    (net (code "20") (name "/SCL1") (class "Default")
      (node (ref "R29") (pin "2") (pinfunction "2_2") (pintype "passive"))
      (node (ref "U12") (pin "1") (pinfunction "SCL_1") (pintype "passive"))
      (node (ref "U18") (pin "D1") (pinfunction "B4_D1") (pintype "passive"))
      (node (ref "U5") (pin "13") (pinfunction "SCX_13") (pintype "input"))
    )
    (net (code "21") (name "/SCL1_1.8V") (class "Default")
      (node (ref "R37") (pin "2") (pinfunction "2_2") (pintype "passive"))
      (node (ref "R41") (pin "2") (pinfunction "2_2") (pintype "passive"))
      (node (ref "R43") (pin "1") (pinfunction "1_1") (pintype "passive"))
      (node (ref "U18") (pin "D3") (pinfunction "A4_D3") (pintype "passive"))
    )
    (net (code "22") (name "/SCL2") (class "Default")
      (node (ref "U4") (pin "2") (pinfunction "SCK_2") (pintype "passive"))
    )
    (net (code "23") (name "/SDA1") (class "Default")
      (node (ref "R30") (pin "2") (pinfunction "2_2") (pintype "passive"))
      (node (ref "U12") (pin "6") (pinfunction "SDA_6") (pintype "passive"))
      (node (ref "U18") (pin "B1") (pinfunction "B2_B1") (pintype "passive"))
      (node (ref "U5") (pin "14") (pinfunction "SDX_14") (pintype "bidirectional"))
    )
    (net (code "24") (name "/SDA1_1.8V") (class "Default")
      (node (ref "R38") (pin "2") (pinfunction "2_2") (pintype "passive"))
      (node (ref "R42") (pin "2") (pinfunction "2_2") (pintype "passive"))
      (node (ref "R46") (pin "1") (pinfunction "1_1") (pintype "passive"))
      (node (ref "U18") (pin "B3") (pinfunction "A2_B3") (pintype "passive"))
    )
    (net (code "25") (name "/SDA2") (class "Default")
      (node (ref "U4") (pin "4") (pinfunction "SDI_4") (pintype "passive"))
    )
    (net (code "26") (name "/Sensor_INT_1.8V") (class "Default")
      (node (ref "R40") (pin "1") (pinfunction "1_1") (pintype "passive"))
      (node (ref "R54") (pin "2") (pinfunction "2_2") (pintype "passive"))
      (node (ref "U7") (pin "13") (pinfunction "~{INT}_13") (pintype "passive"))
    )
    (net (code "27") (name "/Sensor_SCL_1.8V") (class "Default")
      (node (ref "R37") (pin "1") (pinfunction "1_1") (pintype "passive"))
      (node (ref "R55") (pin "2") (pinfunction "2_2") (pintype "passive"))
      (node (ref "U7") (pin "2") (pinfunction "SCL_2") (pintype "passive"))
    )
    (net (code "28") (name "/Sensor_SDA_1.8V") (class "Default")
      (node (ref "R38") (pin "1") (pinfunction "1_1") (pintype "passive"))
      (node (ref "R53") (pin "2") (pinfunction "2_2") (pintype "passive"))
      (node (ref "U7") (pin "3") (pinfunction "SDA_3") (pintype "passive"))
    )
    (net (code "29") (name "1.8V") (class "Default")
      (node (ref "C101") (pin "2") (pinfunction "2_2") (pintype "passive"))
      (node (ref "C102") (pin "1") (pinfunction "1_1") (pintype "passive"))
      (node (ref "C31") (pin "1") (pinfunction "1_1") (pintype "passive"))
      (node (ref "C35") (pin "1") (pinfunction "1_1") (pintype "passive"))
      (node (ref "C40") (pin "1") (pinfunction "1_1") (pintype "passive"))
      (node (ref "C57") (pin "1") (pinfunction "1_1") (pintype "passive"))
      (node (ref "C58") (pin "1") (pinfunction "1_1") (pintype "passive"))
      (node (ref "C61") (pin "1") (pinfunction "1_1") (pintype "passive"))
      (node (ref "C69") (pin "1") (pinfunction "1_1") (pintype "passive"))
      (node (ref "C70") (pin "1") (pinfunction "1_1") (pintype "passive"))
      (node (ref "C79") (pin "1") (pinfunction "1_1") (pintype "passive"))
      (node (ref "C83") (pin "1") (pinfunction "1_1") (pintype "passive"))
      (node (ref "C85") (pin "1") (pinfunction "1_1") (pintype "passive"))
      (node (ref "R35") (pin "1") (pinfunction "1_1") (pintype "passive"))
      (node (ref "R36") (pin "1") (pinfunction "1_1") (pintype "passive"))
      (node (ref "R41") (pin "1") (pinfunction "1_1") (pintype "passive"))
      (node (ref "R42") (pin "1") (pinfunction "1_1") (pintype "passive"))
      (node (ref "R45") (pin "1") (pinfunction "1_1") (pintype "passive"))
      (node (ref "R48") (pin "1") (pinfunction "1_1") (pintype "passive"))
      (node (ref "R49") (pin "1") (pinfunction "1_1") (pintype "passive"))
      (node (ref "R50") (pin "1") (pinfunction "1_1") (pintype "passive"))
      (node (ref "U13") (pin "D6") (pinfunction "DVDD_D6") (pintype "passive"))
      (node (ref "U13") (pin "E1") (pinfunction "AVDD_E1") (pintype "passive"))
      (node (ref "U18") (pin "B2") (pinfunction "VCCA_B2") (pintype "passive"))
      (node (ref "U18") (pin "C2") (pinfunction "EN_C2") (pintype "passive"))
      (node (ref "U3") (pin "11") (pinfunction "VDD_1_11") (pintype "passive"))
      (node (ref "U3") (pin "22") (pinfunction "VDD_2_22") (pintype "passive"))
      (node (ref "U7") (pin "11") (pinfunction "VDD_11") (pintype "passive"))
    )
    (net (code "30") (name "3.3V") (class "Default")
      (node (ref "C105") (pin "1") (pinfunction "1_1") (pintype "passive"))
      (node (ref "C37") (pin "1") (pinfunction "1_1") (pintype "passive"))
      (node (ref "C50") (pin "1") (pinfunction "1_1") (pintype "passive"))
      (node (ref "C55") (pin "1") (pinfunction "1_1") (pintype "passive"))
      (node (ref "C56") (pin "1") (pinfunction "1_1") (pintype "passive"))
      (node (ref "C68") (pin "1") (pinfunction "1_1") (pintype "passive"))
      (node (ref "C75") (pin "1") (pinfunction "1_1") (pintype "passive"))
      (node (ref "C97") (pin "2") (pinfunction "2_2") (pintype "passive"))
      (node (ref "C98") (pin "1") (pinfunction "1_1") (pintype "passive"))
      (node (ref "D3") (pin "2") (pinfunction "K_2") (pintype "passive"))
      (node (ref "LS1") (pin "2") (pinfunction "+_2") (pintype "passive"))
      (node (ref "R24") (pin "1") (pinfunction "1_1") (pintype "passive"))
      (node (ref "R28") (pin "1") (pinfunction "1_1") (pintype "passive"))
      (node (ref "R29") (pin "1") (pinfunction "1_1") (pintype "passive"))
      (node (ref "R30") (pin "1") (pinfunction "1_1") (pintype "passive"))
      (node (ref "R33") (pin "1") (pinfunction "1_1") (pintype "passive"))
      (node (ref "R60") (pin "1") (pinfunction "1_1") (pintype "passive"))
      (node (ref "R61") (pin "1") (pinfunction "1_1") (pintype "passive"))
      (node (ref "U12") (pin "5") (pinfunction "V+_5") (pintype "passive"))
      (node (ref "U13") (pin "D3") (pinfunction "OVDD_D3") (pintype "passive"))
      (node (ref "U18") (pin "A2") (pinfunction "VCCB_A2") (pintype "passive"))
      (node (ref "U4") (pin "1") (pinfunction "VDDIO_1") (pintype "passive"))
      (node (ref "U4") (pin "10") (pinfunction "VDD_10") (pintype "passive"))
      (node (ref "U4") (pin "6") (pinfunction "CSB_6") (pintype "passive"))
      (node (ref "X4") (pin "4") (pinfunction "VDD_4") (pintype "passive"))
    )
    (net (code "31") (name "5V_MAX") (class "Default")
      (node (ref "C100") (pin "1") (pinfunction "1_1") (pintype "passive"))
      (node (ref "C24") (pin "1") (pinfunction "1_1") (pintype "passive"))
      (node (ref "C39") (pin "1") (pinfunction "1_1") (pintype "passive"))
      (node (ref "C84") (pin "1") (pinfunction "1_1") (pintype "passive"))
      (node (ref "C99") (pin "2") (pinfunction "2_2") (pintype "passive"))
      (node (ref "U7") (pin "10") (pinfunction "VLED+_2_10") (pintype "passive"))
      (node (ref "U7") (pin "9") (pinfunction "VLED+_1_9") (pintype "passive"))
    )
    (net (code "32") (name "GND") (class "Default")
      (node (ref "C100") (pin "2") (pinfunction "2_2") (pintype "passive"))
      (node (ref "C101") (pin "1") (pinfunction "1_1") (pintype "passive"))
      (node (ref "C102") (pin "2") (pinfunction "2_2") (pintype "passive"))
      (node (ref "C105") (pin "2") (pinfunction "2_2") (pintype "passive"))
      (node (ref "C106") (pin "2") (pinfunction "2_2") (pintype "passive"))
      (node (ref "C24") (pin "2") (pinfunction "2_2") (pintype "passive"))
      (node (ref "C29") (pin "2") (pinfunction "2_2") (pintype "passive"))
      (node (ref "C31") (pin "2") (pinfunction "2_2") (pintype "passive"))
      (node (ref "C35") (pin "2") (pinfunction "2_2") (pintype "passive"))
      (node (ref "C37") (pin "2") (pinfunction "2_2") (pintype "passive"))
      (node (ref "C39") (pin "2") (pinfunction "2_2") (pintype "passive"))
      (node (ref "C40") (pin "2") (pinfunction "2_2") (pintype "passive"))
      (node (ref "C48") (pin "2") (pinfunction "2_2") (pintype "passive"))
      (node (ref "C49") (pin "2") (pinfunction "2_2") (pintype "passive"))
      (node (ref "C50") (pin "2") (pinfunction "2_2") (pintype "passive"))
      (node (ref "C51") (pin "1") (pinfunction "1_1") (pintype "passive"))
      (node (ref "C52") (pin "2") (pinfunction "2_2") (pintype "passive"))
      (node (ref "C53") (pin "1") (pinfunction "1_1") (pintype "passive"))
      (node (ref "C54") (pin "2") (pinfunction "2_2") (pintype "passive"))
      (node (ref "C55") (pin "2") (pinfunction "2_2") (pintype "passive"))
      (node (ref "C56") (pin "2") (pinfunction "2_2") (pintype "passive"))
      (node (ref "C57") (pin "2") (pinfunction "2_2") (pintype "passive"))
      (node (ref "C58") (pin "2") (pinfunction "2_2") (pintype "passive"))
      (node (ref "C61") (pin "2") (pinfunction "2_2") (pintype "passive"))
      (node (ref "C62") (pin "2") (pinfunction "2_2") (pintype "passive"))
      (node (ref "C63") (pin "2") (pinfunction "2_2") (pintype "passive"))
      (node (ref "C64") (pin "2") (pinfunction "2_2") (pintype "passive"))
      (node (ref "C65") (pin "2") (pinfunction "2_2") (pintype "passive"))
      (node (ref "C68") (pin "2") (pinfunction "2_2") (pintype "passive"))
      (node (ref "C69") (pin "2") (pinfunction "2_2") (pintype "passive"))
      (node (ref "C70") (pin "2") (pinfunction "2_2") (pintype "passive"))
      (node (ref "C75") (pin "2") (pinfunction "2_2") (pintype "passive"))
      (node (ref "C79") (pin "2") (pinfunction "2_2") (pintype "passive"))
      (node (ref "C83") (pin "2") (pinfunction "2_2") (pintype "passive"))
      (node (ref "C84") (pin "2") (pinfunction "2_2") (pintype "passive"))
      (node (ref "C85") (pin "2") (pinfunction "2_2") (pintype "passive"))
      (node (ref "C97") (pin "1") (pinfunction "1_1") (pintype "passive"))
      (node (ref "C98") (pin "2") (pinfunction "2_2") (pintype "passive"))
      (node (ref "C99") (pin "1") (pinfunction "1_1") (pintype "passive"))
      (node (ref "Q4") (pin "S") (pinfunction "S_S") (pintype "passive"))
      (node (ref "R12") (pin "1") (pinfunction "1_1") (pintype "passive"))
      (node (ref "R23") (pin "2") (pinfunction "2_2") (pintype "passive"))
      (node (ref "R26") (pin "1") (pinfunction "1_1") (pintype "passive"))
      (node (ref "R34") (pin "2") (pinfunction "2_2") (pintype "passive"))
      (node (ref "R52") (pin "2") (pinfunction "2_2") (pintype "passive"))
      (node (ref "U11") (pin "2") (pinfunction "A_2") (pintype "passive"))
      (node (ref "U12") (pin "2") (pinfunction "GND_2") (pintype "passive"))
      (node (ref "U13") (pin "B3") (pinfunction "AGND_B3") (pintype "passive"))
      (node (ref "U13") (pin "B4") (pinfunction "AGND_B4") (pintype "passive"))
      (node (ref "U13") (pin "C3") (pinfunction "AGND_C3") (pintype "passive"))
      (node (ref "U13") (pin "C4") (pinfunction "AGND_C4") (pintype "passive"))
      (node (ref "U13") (pin "C5") (pinfunction "DGND_C5") (pintype "passive"))
      (node (ref "U13") (pin "D4") (pinfunction "AGND_D4") (pintype "passive"))
      (node (ref "U18") (pin "D2") (pinfunction "GND_D2") (pintype "passive"))
      (node (ref "U3") (pin "10") (pinfunction "VSS_2_10") (pintype "passive"))
      (node (ref "U3") (pin "25") (pinfunction "EP_25") (pintype "passive"))
      (node (ref "U3") (pin "7") (pinfunction "VSS_1_7") (pintype "passive"))
      (node (ref "U4") (pin "3") (pinfunction "VSS_1_3") (pintype "passive"))
      (node (ref "U4") (pin "5") (pinfunction "SDO_5") (pintype "passive"))
      (node (ref "U4") (pin "8") (pinfunction "VSS_2_8") (pintype "passive"))
      (node (ref "U4") (pin "9") (pinfunction "VSS_3_9") (pintype "passive"))
      (node (ref "U5") (pin "1") (pinfunction "SDO_1") (pintype "bidirectional"))
      (node (ref "U5") (pin "6") (pinfunction "GNDIO_6") (pintype "power_in"))
      (node (ref "U5") (pin "7") (pinfunction "GND_7") (pintype "power_in"))
      (node (ref "U7") (pin "12") (pinfunction "GND_12") (pintype "passive"))
      (node (ref "U7") (pin "4") (pinfunction "PGND_4") (pintype "passive"))
      (node (ref "X4") (pin "2") (pinfunction "GND_2") (pintype "passive"))
    )
    (net (code "33") (name "Net-(C59-Pad2)") (class "Default")
      (node (ref "C59") (pin "2") (pinfunction "2_2") (pintype "passive"))
      (node (ref "R34") (pin "1") (pinfunction "1_1") (pintype "passive"))
    )
    (net (code "34") (name "Net-(D3-A)") (class "Default")
      (node (ref "D3") (pin "1") (pinfunction "A_1") (pintype "passive"))
      (node (ref "LS1") (pin "1") (pinfunction "-_1") (pintype "passive"))
      (node (ref "Q4") (pin "D") (pinfunction "D_D") (pintype "passive"))
    )
    (net (code "35") (name "Net-(Q4-PadG)") (class "Default")
      (node (ref "Q4") (pin "G") (pinfunction "G_G") (pintype "passive"))
      (node (ref "R22") (pin "2") (pinfunction "2_2") (pintype "passive"))
      (node (ref "R23") (pin "1") (pinfunction "1_1") (pintype "passive"))
    )
    (net (code "36") (name "Net-(U3-32KIN)") (class "Default")
      (node (ref "U3") (pin "9") (pinfunction "32KIN_9") (pintype "passive"))
      (node (ref "X3") (pin "2") (pinfunction "out_2") (pintype "passive"))
    )
    (net (code "37") (name "Net-(U3-32KOUT)") (class "Default")
      (node (ref "U3") (pin "8") (pinfunction "32KOUT_8") (pintype "passive"))
      (node (ref "X3") (pin "1") (pinfunction "inp_1") (pintype "passive"))
    )
    (net (code "38") (name "Net-(U3-ACCEL_INT)") (class "Default")
      (node (ref "R36") (pin "2") (pinfunction "2_2") (pintype "passive"))
      (node (ref "R52") (pin "1") (pinfunction "1_1") (pintype "passive"))
      (node (ref "R59") (pin "1") (pinfunction "1_1") (pintype "passive"))
      (node (ref "U3") (pin "19") (pinfunction "ACCEL_INT_19") (pintype "passive"))
    )
    (net (code "39") (name "Net-(U3-HR_INT)") (class "Default")
      (node (ref "R50") (pin "2") (pinfunction "2_2") (pintype "passive"))
      (node (ref "R54") (pin "1") (pinfunction "1_1") (pintype "passive"))
      (node (ref "U3") (pin "18") (pinfunction "HR_INT_18") (pintype "passive"))
    )
    (net (code "40") (name "Net-(U3-MFIO)") (class "Default")
      (node (ref "R44") (pin "2") (pinfunction "2_2") (pintype "passive"))
      (node (ref "U3") (pin "1") (pinfunction "MFIO_1") (pintype "passive"))
    )
    (net (code "41") (name "Net-(U3-RSTN)") (class "Default")
      (node (ref "C59") (pin "1") (pinfunction "1_1") (pintype "passive"))
      (node (ref "R47") (pin "2") (pinfunction "2_2") (pintype "passive"))
      (node (ref "U3") (pin "6") (pinfunction "RSTN_6") (pintype "passive"))
    )
    (net (code "42") (name "Net-(U3-SENSOR_SCL)") (class "Default")
      (node (ref "R48") (pin "2") (pinfunction "2_2") (pintype "passive"))
      (node (ref "R55") (pin "1") (pinfunction "1_1") (pintype "passive"))
      (node (ref "U3") (pin "14") (pinfunction "SENSOR_SCL_14") (pintype "passive"))
    )
    (net (code "43") (name "Net-(U3-SENSOR_SDA)") (class "Default")
      (node (ref "R49") (pin "2") (pinfunction "2_2") (pintype "passive"))
      (node (ref "R53") (pin "1") (pinfunction "1_1") (pintype "passive"))
      (node (ref "U3") (pin "13") (pinfunction "SENSOR_SDA_13") (pintype "passive"))
    )
    (net (code "44") (name "Net-(U3-SLAVE_SCL)") (class "Default")
      (node (ref "R43") (pin "2") (pinfunction "2_2") (pintype "passive"))
      (node (ref "U3") (pin "24") (pinfunction "SLAVE_SCL_24") (pintype "passive"))
    )
    (net (code "45") (name "Net-(U3-SLAVE_SDA)") (class "Default")
      (node (ref "R46") (pin "2") (pinfunction "2_2") (pintype "passive"))
      (node (ref "U3") (pin "23") (pinfunction "SLAVE_SDA_23") (pintype "passive"))
    )
    (net (code "46") (name "Net-(U3-VCORE)") (class "Default")
      (node (ref "C29") (pin "1") (pinfunction "1_1") (pintype "passive"))
      (node (ref "C62") (pin "1") (pinfunction "1_1") (pintype "passive"))
      (node (ref "U3") (pin "12") (pinfunction "VCORE_12") (pintype "passive"))
    )
    (net (code "47") (name "Net-(U12-ADD0)") (class "Default")
      (node (ref "R12") (pin "2") (pinfunction "2_2") (pintype "passive"))
      (node (ref "U12") (pin "4") (pinfunction "ADD0_4") (pintype "passive"))
    )
    (net (code "48") (name "Net-(U13-BIN)") (class "Default")
      (node (ref "C54") (pin "1") (pinfunction "1_1") (pintype "passive"))
      (node (ref "C71") (pin "1") (pinfunction "1_1") (pintype "passive"))
      (node (ref "R57") (pin "2") (pinfunction "2_2") (pintype "passive"))
      (node (ref "U13") (pin "A3") (pinfunction "BIN_A3") (pintype "passive"))
    )
    (net (code "49") (name "Net-(U13-BIP)") (class "Default")
      (node (ref "C53") (pin "2") (pinfunction "2_2") (pintype "passive"))
      (node (ref "C71") (pin "2") (pinfunction "2_2") (pintype "passive"))
      (node (ref "R39") (pin "2") (pinfunction "2_2") (pintype "passive"))
      (node (ref "U13") (pin "A4") (pinfunction "BIP_A4") (pintype "passive"))
    )
    (net (code "50") (name "Net-(U13-CAPN)") (class "Default")
      (node (ref "C60") (pin "2") (pinfunction "2_2") (pintype "passive"))
      (node (ref "U13") (pin "B5") (pinfunction "CAPN_B5") (pintype "passive"))
    )
    (net (code "51") (name "Net-(U13-CAPP)") (class "Default")
      (node (ref "C60") (pin "1") (pinfunction "1_1") (pintype "passive"))
      (node (ref "U13") (pin "B6") (pinfunction "CAPP_B6") (pintype "passive"))
    )
    (net (code "52") (name "Net-(U13-CPLL)") (class "Default")
      (node (ref "C65") (pin "1") (pinfunction "1_1") (pintype "passive"))
      (node (ref "U13") (pin "C6") (pinfunction "CPLL_C6") (pintype "passive"))
    )
    (net (code "53") (name "Net-(U13-DRVN)") (class "Default")
      (node (ref "C82") (pin "1") (pinfunction "1_1") (pintype "passive"))
      (node (ref "U13") (pin "A2") (pinfunction "DRVN_A2") (pintype "passive"))
    )
    (net (code "54") (name "Net-(U13-DRVP)") (class "Default")
      (node (ref "C76") (pin "1") (pinfunction "1_1") (pintype "passive"))
      (node (ref "U13") (pin "A1") (pinfunction "DRVP_A1") (pintype "passive"))
    )
    (net (code "55") (name "Net-(U13-ECGN)") (class "Default")
      (node (ref "C38") (pin "1") (pinfunction "1_1") (pintype "passive"))
      (node (ref "C52") (pin "1") (pinfunction "1_1") (pintype "passive"))
      (node (ref "R58") (pin "2") (pinfunction "2_2") (pintype "passive"))
      (node (ref "U13") (pin "A6") (pinfunction "ECGN_A6") (pintype "passive"))
    )
    (net (code "56") (name "Net-(U13-ECGP)") (class "Default")
      (node (ref "C38") (pin "2") (pinfunction "2_2") (pintype "passive"))
      (node (ref "C51") (pin "2") (pinfunction "2_2") (pintype "passive"))
      (node (ref "R2") (pin "2") (pinfunction "2_2") (pintype "passive"))
      (node (ref "U13") (pin "A5") (pinfunction "ECGP_A5") (pintype "passive"))
    )
    (net (code "57") (name "Net-(U13-RBIAS)") (class "Default")
      (node (ref "R26") (pin "2") (pinfunction "2_2") (pintype "passive"))
      (node (ref "U13") (pin "B2") (pinfunction "RBIAS_B2") (pintype "passive"))
    )
    (net (code "58") (name "Net-(U13-VBG)") (class "Default")
      (node (ref "C63") (pin "1") (pinfunction "1_1") (pintype "passive"))
      (node (ref "U13") (pin "B1") (pinfunction "VBG_B1") (pintype "passive"))
    )
    (net (code "59") (name "Net-(U13-VCM)") (class "Default")
      (node (ref "C106") (pin "1") (pinfunction "1_1") (pintype "passive"))
      (node (ref "R68") (pin "1") (pinfunction "1_1") (pintype "passive"))
      (node (ref "U13") (pin "C1") (pinfunction "VCM_C1") (pintype "passive"))
    )
    (net (code "60") (name "Net-(U13-VREF)") (class "Default")
      (node (ref "C64") (pin "1") (pinfunction "1_1") (pintype "passive"))
      (node (ref "U13") (pin "D1") (pinfunction "VREF_D1") (pintype "passive"))
    )
    (net (code "61") (name "Net-(X4-CLK_OUT)") (class "Default")
      (node (ref "R69") (pin "1") (pinfunction "1_1") (pintype "passive"))
      (node (ref "X4") (pin "3") (pinfunction "CLK_OUT_3") (pintype "passive"))
    )
    (net (code "62") (name "unconnected-(U3-D.N.C._1-Pad2)") (class "Default")
      (node (ref "U3") (pin "2") (pinfunction "D.N.C._1_2") (pintype "passive"))
    )
    (net (code "63") (name "unconnected-(U3-D.N.C._2-Pad4)") (class "Default")
      (node (ref "U3") (pin "4") (pinfunction "D.N.C._2_4") (pintype "passive"))
    )
    (net (code "64") (name "unconnected-(U3-D.N.C._3-Pad5)") (class "Default")
      (node (ref "U3") (pin "5") (pinfunction "D.N.C._3_5") (pintype "passive"))
    )
    (net (code "65") (name "unconnected-(U3-D.N.C._4-Pad20)") (class "Default")
      (node (ref "U3") (pin "20") (pinfunction "D.N.C._4_20") (pintype "passive"))
    )
    (net (code "66") (name "unconnected-(U3-D.N.C._5-Pad21)") (class "Default")
      (node (ref "U3") (pin "21") (pinfunction "D.N.C._5_21") (pintype "passive"))
    )
    (net (code "67") (name "unconnected-(U3-D.N.C_1-Pad16)") (class "Default")
      (node (ref "U3") (pin "16") (pinfunction "D.N.C_1_16") (pintype "passive"))
    )
    (net (code "68") (name "unconnected-(U3-D.N.C_2-Pad17)") (class "Default")
      (node (ref "U3") (pin "17") (pinfunction "D.N.C_2_17") (pintype "passive"))
    )
    (net (code "69") (name "unconnected-(U3-NC_1-Pad3)") (class "Default")
      (node (ref "U3") (pin "3") (pinfunction "NC_1_3") (pintype "passive"))
    )
    (net (code "70") (name "unconnected-(U3-NC_2-Pad15)") (class "Default")
      (node (ref "U3") (pin "15") (pinfunction "NC_2_15") (pintype "passive"))
    )
    (net (code "71") (name "unconnected-(U5-ASCX-Pad3)") (class "Default")
      (node (ref "U5") (pin "3") (pinfunction "ASCX_3") (pintype "bidirectional"))
    )
    (net (code "72") (name "unconnected-(U5-ASDX-Pad2)") (class "Default")
      (node (ref "U5") (pin "2") (pinfunction "ASDX_2") (pintype "bidirectional"))
    )
    (net (code "73") (name "unconnected-(U5-OSCB-Pad10)") (class "Default")
      (node (ref "U5") (pin "10") (pinfunction "OSCB_10") (pintype "passive"))
    )
    (net (code "74") (name "unconnected-(U5-OSDO-Pad11)") (class "Default")
      (node (ref "U5") (pin "11") (pinfunction "OSDO_11") (pintype "output"))
    )
    (net (code "75") (name "unconnected-(U7-N.C._1-Pad1)") (class "Default")
      (node (ref "U7") (pin "1") (pinfunction "N.C._1_1") (pintype "passive"))
    )
    (net (code "76") (name "unconnected-(U7-N.C._2-Pad5)") (class "Default")
      (node (ref "U7") (pin "5") (pinfunction "N.C._2_5") (pintype "passive"))
    )
    (net (code "77") (name "unconnected-(U7-N.C._3-Pad6)") (class "Default")
      (node (ref "U7") (pin "6") (pinfunction "N.C._3_6") (pintype "passive"))
    )
    (net (code "78") (name "unconnected-(U7-N.C._4-Pad7)") (class "Default")
      (node (ref "U7") (pin "7") (pinfunction "N.C._4_7") (pintype "passive"))
    )
    (net (code "79") (name "unconnected-(U7-N.C._5-Pad8)") (class "Default")
      (node (ref "U7") (pin "8") (pinfunction "N.C._5_8") (pintype "passive"))
    )
    (net (code "80") (name "unconnected-(U7-N.C._6-Pad14)") (class "Default")
      (node (ref "U7") (pin "14") (pinfunction "N.C._6_14") (pintype "passive"))
    )
    (net (code "81") (name "unconnected-(U11-C-Pad1)") (class "Default")
      (node (ref "U11") (pin "1") (pinfunction "C_1") (pintype "passive"))
    )
    (net (code "82") (name "unconnected-(U11-C-Pad3)") (class "Default")
      (node (ref "U11") (pin "3") (pinfunction "C_3") (pintype "passive"))
    )
    (net (code "83") (name "unconnected-(U12-ALERT-Pad3)") (class "Default")
      (node (ref "U12") (pin "3") (pinfunction "ALERT_3") (pintype "passive"))
    )
    (net (code "84") (name "unconnected-(U12-EP-Pad7)") (class "Default")
      (node (ref "U12") (pin "7") (pinfunction "EP_7") (pintype "passive"))
    )
    (net (code "85") (name "unconnected-(U13-AOUT-PadC2)") (class "Default")
      (node (ref "U13") (pin "C2") (pinfunction "AOUT_C2") (pintype "passive"))
    )
    (net (code "86") (name "unconnected-(X4-NC-Pad1)") (class "Default")
      (node (ref "X4") (pin "1") (pinfunction "NC_1") (pintype "passive"))
    )
  )
)
